# arduino_uno_shield.net
KiCad netlist of a schematic drawn in EAGLE
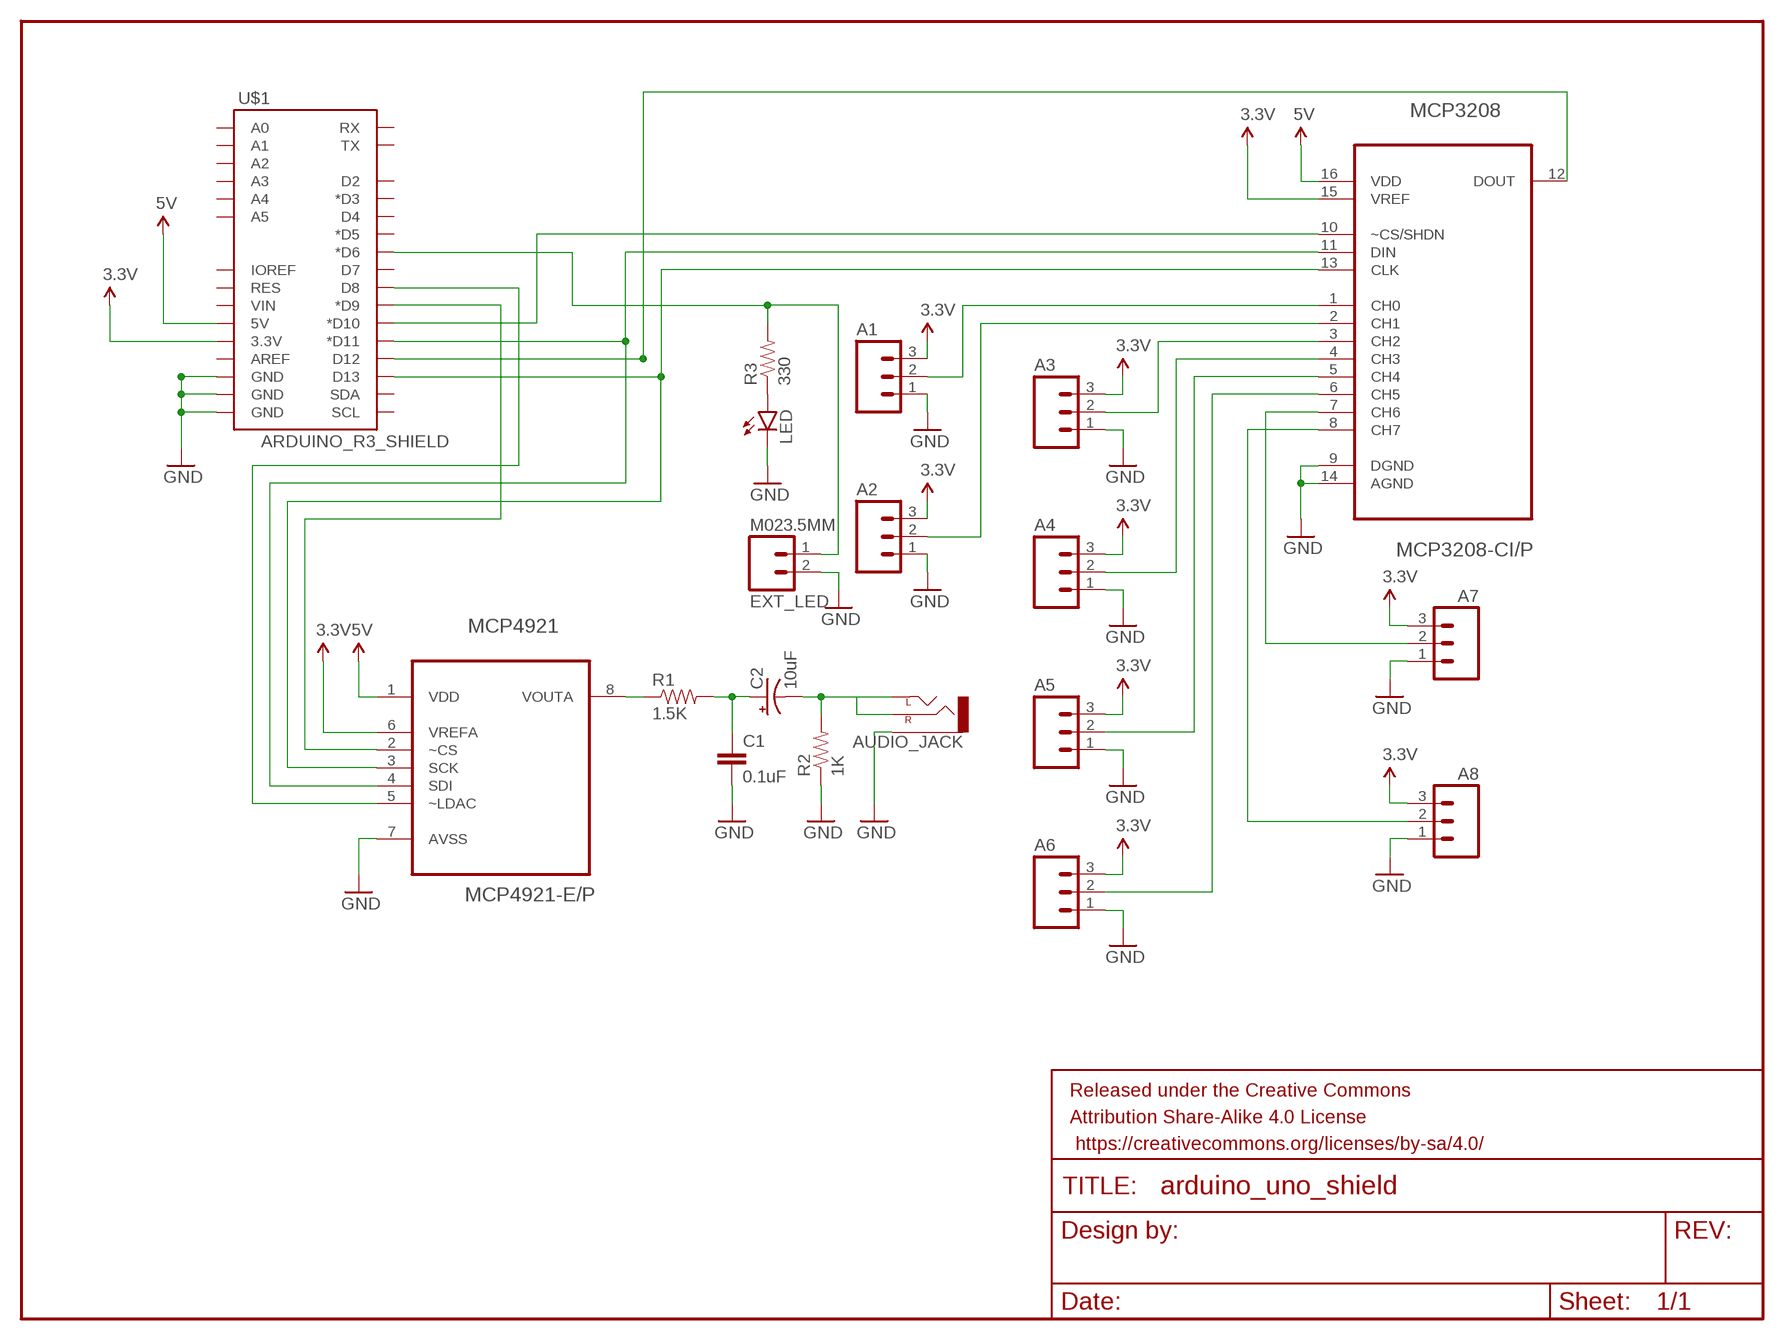
[diagram p0: schematic, sheet 1]

(export (version "E")
  (design (tool "Eeschema 10.0.6"))
  (components
    (comp (ref "A1")
      (value "M03PTH")
      (footprint "eagle-import:1X03")
      (libsource (lib "eagle-import") (part "M03PTH"))
    )
    (comp (ref "A2")
      (value "M03PTH")
      (footprint "eagle-import:1X03")
      (libsource (lib "eagle-import") (part "M03PTH"))
    )
    (comp (ref "A3")
      (value "M03PTH")
      (footprint "eagle-import:1X03")
      (libsource (lib "eagle-import") (part "M03PTH"))
    )
    (comp (ref "A4")
      (value "M03PTH")
      (footprint "eagle-import:1X03")
      (libsource (lib "eagle-import") (part "M03PTH"))
    )
    (comp (ref "A5")
      (value "M03PTH")
      (footprint "eagle-import:1X03")
      (libsource (lib "eagle-import") (part "M03PTH"))
    )
    (comp (ref "A6")
      (value "M03PTH")
      (footprint "eagle-import:1X03")
      (libsource (lib "eagle-import") (part "M03PTH"))
    )
    (comp (ref "A7")
      (value "M03PTH")
      (footprint "eagle-import:1X03")
      (libsource (lib "eagle-import") (part "M03PTH"))
    )
    (comp (ref "A8")
      (value "M03PTH")
      (footprint "eagle-import:1X03")
      (libsource (lib "eagle-import") (part "M03PTH"))
    )
    (comp (ref "AUDIO_JACK")
      (value "AUDIO-JACKPTH")
      (footprint "eagle-import:AUDIO-JACK")
      (libsource (lib "eagle-import") (part "AUDIO-JACKPTH"))
    )
    (comp (ref "C1")
      (value "0.1uF")
      (footprint "eagle-import:CAP-PTH-SMALL")
      (libsource (lib "eagle-import") (part "CAPPTH"))
    )
    (comp (ref "C2")
      (value "10uF")
      (footprint "eagle-import:CPOL-RADIAL-10UF-25V")
      (libsource (lib "eagle-import") (part "CAP_POLPTH2"))
    )
    (comp (ref "EXT_LED")
      (value "M023.5MM")
      (footprint "eagle-import:SCREWTERMINAL-3.5MM-2")
      (libsource (lib "eagle-import") (part "M023.5MM"))
    )
    (comp (ref "FRAME3")
      (value "FRAME-LETTER")
      (footprint "eagle-import:CREATIVE_COMMONS")
      (libsource (lib "eagle-import") (part "FRAME-LETTER"))
    )
    (comp (ref "LED")
      (value "LED5MM")
      (footprint "eagle-import:LED5MM")
      (libsource (lib "eagle-import") (part "LED5MM"))
    )
    (comp (ref "MCP3208")
      (value "MCP3208-CI/P")
      (footprint "eagle-import:DIP254P762X432-16")
      (libsource (lib "eagle-import") (part "MCP3208-CI/P"))
    )
    (comp (ref "MCP4921")
      (value "MCP4921-E/P")
      (footprint "eagle-import:DIP254P762X432-8")
      (libsource (lib "eagle-import") (part "MCP4921-E/P"))
    )
    (comp (ref "R1")
      (value "1.5K")
      (footprint "eagle-import:AXIAL-0.4")
      (libsource (lib "eagle-import") (part "RESISTORPTH-1/4W"))
    )
    (comp (ref "R2")
      (value "1K")
      (footprint "eagle-import:AXIAL-0.4")
      (libsource (lib "eagle-import") (part "RESISTORPTH-1/4W"))
    )
    (comp (ref "R3")
      (value "330")
      (footprint "eagle-import:AXIAL-0.4")
      (libsource (lib "eagle-import") (part "RESISTORPTH-1/4W"))
    )
    (comp (ref "U$1")
      (value "ARDUINO_R3_SHIELD")
      (footprint "eagle-import:UNO_R3_SHIELD")
      (libsource (lib "eagle-import") (part "ARDUINO_R3_SHIELD"))
    )
  )
  (nets
    (net (code "1") (name "3.3V") (class "Default")
      (node (ref "A1") (pin "3") (pinfunction "3_3") (pintype "passive"))
      (node (ref "A2") (pin "3") (pinfunction "3_3") (pintype "passive"))
      (node (ref "A3") (pin "3") (pinfunction "3_3") (pintype "passive"))
      (node (ref "A4") (pin "3") (pinfunction "3_3") (pintype "passive"))
      (node (ref "A5") (pin "3") (pinfunction "3_3") (pintype "passive"))
      (node (ref "A6") (pin "3") (pinfunction "3_3") (pintype "passive"))
      (node (ref "A7") (pin "3") (pinfunction "3_3") (pintype "passive"))
      (node (ref "A8") (pin "3") (pinfunction "3_3") (pintype "passive"))
      (node (ref "MCP3208") (pin "15") (pinfunction "VREF_15") (pintype "power_in"))
      (node (ref "MCP4921") (pin "6") (pinfunction "VREFA_6") (pintype "input"))
      (node (ref "U$1") (pin "3.3V") (pinfunction "3.3V_3.3V") (pintype "bidirectional"))
    )
    (net (code "2") (name "5V") (class "Default")
      (node (ref "MCP3208") (pin "16") (pinfunction "VDD_16") (pintype "power_in"))
      (node (ref "MCP4921") (pin "1") (pinfunction "VDD_1") (pintype "power_in"))
      (node (ref "U$1") (pin "5V") (pinfunction "5V_5V") (pintype "bidirectional"))
    )
    (net (code "3") (name "GND") (class "Default")
      (node (ref "A1") (pin "1") (pinfunction "1_1") (pintype "passive"))
      (node (ref "A2") (pin "1") (pinfunction "1_1") (pintype "passive"))
      (node (ref "A3") (pin "1") (pinfunction "1_1") (pintype "passive"))
      (node (ref "A4") (pin "1") (pinfunction "1_1") (pintype "passive"))
      (node (ref "A5") (pin "1") (pinfunction "1_1") (pintype "passive"))
      (node (ref "A6") (pin "1") (pinfunction "1_1") (pintype "passive"))
      (node (ref "A7") (pin "1") (pinfunction "1_1") (pintype "passive"))
      (node (ref "A8") (pin "1") (pinfunction "1_1") (pintype "passive"))
      (node (ref "AUDIO_JACK") (pin "SLEEVE") (pinfunction "SLEEVE_SLEEVE") (pintype "bidirectional"))
      (node (ref "C1") (pin "2") (pinfunction "2_2") (pintype "passive"))
      (node (ref "EXT_LED") (pin "2") (pinfunction "2_2") (pintype "passive"))
      (node (ref "LED") (pin "K") (pinfunction "C_K") (pintype "passive"))
      (node (ref "MCP3208") (pin "14") (pinfunction "AGND_14") (pintype "passive"))
      (node (ref "MCP3208") (pin "9") (pinfunction "DGND_9") (pintype "passive"))
      (node (ref "MCP4921") (pin "7") (pinfunction "AVSS_7") (pintype "passive"))
      (node (ref "R2") (pin "P$1") (pinfunction "1_P$1") (pintype "passive"))
      (node (ref "U$1") (pin "GND@0") (pinfunction "GND_GND@0") (pintype "bidirectional"))
      (node (ref "U$1") (pin "GND@1") (pinfunction "GND_GND@1") (pintype "bidirectional"))
      (node (ref "U$1") (pin "GND@2") (pinfunction "GND_GND@2") (pintype "bidirectional"))
    )
    (net (code "4") (name "Net-(AUDIO_JACK-LEFT)") (class "Default")
      (node (ref "AUDIO_JACK") (pin "RING") (pinfunction "RIGHT_RING") (pintype "bidirectional"))
      (node (ref "AUDIO_JACK") (pin "TIP") (pinfunction "LEFT_TIP") (pintype "bidirectional"))
      (node (ref "C2") (pin "2") (pinfunction "-_2") (pintype "passive"))
      (node (ref "R2") (pin "P$2") (pinfunction "2_P$2") (pintype "passive"))
    )
    (net (code "5") (name "Net-(C2-+)") (class "Default")
      (node (ref "C1") (pin "1") (pinfunction "1_1") (pintype "passive"))
      (node (ref "C2") (pin "1") (pinfunction "+_1") (pintype "passive"))
      (node (ref "R1") (pin "P$2") (pinfunction "2_P$2") (pintype "passive"))
    )
    (net (code "6") (name "Net-(MCP3208-CH0)") (class "Default")
      (node (ref "A1") (pin "2") (pinfunction "2_2") (pintype "passive"))
      (node (ref "MCP3208") (pin "1") (pinfunction "CH0_1") (pintype "input"))
    )
    (net (code "7") (name "Net-(MCP3208-CH1)") (class "Default")
      (node (ref "A2") (pin "2") (pinfunction "2_2") (pintype "passive"))
      (node (ref "MCP3208") (pin "2") (pinfunction "CH1_2") (pintype "input"))
    )
    (net (code "8") (name "Net-(MCP3208-CH2)") (class "Default")
      (node (ref "A3") (pin "2") (pinfunction "2_2") (pintype "passive"))
      (node (ref "MCP3208") (pin "3") (pinfunction "CH2_3") (pintype "input"))
    )
    (net (code "9") (name "Net-(MCP3208-CH3)") (class "Default")
      (node (ref "A4") (pin "2") (pinfunction "2_2") (pintype "passive"))
      (node (ref "MCP3208") (pin "4") (pinfunction "CH3_4") (pintype "input"))
    )
    (net (code "10") (name "Net-(MCP3208-CH4)") (class "Default")
      (node (ref "A5") (pin "2") (pinfunction "2_2") (pintype "passive"))
      (node (ref "MCP3208") (pin "5") (pinfunction "CH4_5") (pintype "input"))
    )
    (net (code "11") (name "Net-(MCP3208-CH5)") (class "Default")
      (node (ref "A6") (pin "2") (pinfunction "2_2") (pintype "passive"))
      (node (ref "MCP3208") (pin "6") (pinfunction "CH5_6") (pintype "input"))
    )
    (net (code "12") (name "Net-(MCP3208-CH6)") (class "Default")
      (node (ref "A7") (pin "2") (pinfunction "2_2") (pintype "passive"))
      (node (ref "MCP3208") (pin "7") (pinfunction "CH6_7") (pintype "input"))
    )
    (net (code "13") (name "Net-(MCP3208-CH7)") (class "Default")
      (node (ref "A8") (pin "2") (pinfunction "2_2") (pintype "passive"))
      (node (ref "MCP3208") (pin "8") (pinfunction "CH7_8") (pintype "input"))
    )
    (net (code "14") (name "Net-(MCP3208-CLK)") (class "Default")
      (node (ref "MCP3208") (pin "13") (pinfunction "CLK_13") (pintype "input"))
      (node (ref "MCP4921") (pin "3") (pinfunction "SCK_3") (pintype "input"))
      (node (ref "U$1") (pin "D13") (pinfunction "D13_D13") (pintype "bidirectional"))
    )
    (net (code "15") (name "Net-(MCP3208-DIN)") (class "Default")
      (node (ref "MCP3208") (pin "11") (pinfunction "DIN_11") (pintype "input"))
      (node (ref "MCP4921") (pin "4") (pinfunction "SDI_4") (pintype "input"))
      (node (ref "U$1") (pin "D11") (pinfunction "*D11_D11") (pintype "bidirectional"))
    )
    (net (code "16") (name "Net-(MCP3208-DOUT)") (class "Default")
      (node (ref "MCP3208") (pin "12") (pinfunction "DOUT_12") (pintype "output"))
      (node (ref "U$1") (pin "D12") (pinfunction "D12_D12") (pintype "bidirectional"))
    )
    (net (code "17") (name "Net-(MCP3208-~{CS{slash}SHDN})") (class "Default")
      (node (ref "MCP3208") (pin "10") (pinfunction "~{CS/SHDN}_10") (pintype "input"))
      (node (ref "U$1") (pin "D10") (pinfunction "*D10_D10") (pintype "bidirectional"))
    )
    (net (code "18") (name "Net-(MCP4921-VOUTA)") (class "Default")
      (node (ref "MCP4921") (pin "8") (pinfunction "VOUTA_8") (pintype "output"))
      (node (ref "R1") (pin "P$1") (pinfunction "1_P$1") (pintype "passive"))
    )
    (net (code "19") (name "Net-(MCP4921-~{CS})") (class "Default")
      (node (ref "MCP4921") (pin "2") (pinfunction "~{CS}_2") (pintype "input"))
      (node (ref "U$1") (pin "D9") (pinfunction "*D9_D9") (pintype "bidirectional"))
    )
    (net (code "20") (name "Net-(MCP4921-~{LDAC})") (class "Default")
      (node (ref "MCP4921") (pin "5") (pinfunction "~{LDAC}_5") (pintype "input"))
      (node (ref "U$1") (pin "D8") (pinfunction "D8_D8") (pintype "bidirectional"))
    )
    (net (code "21") (name "Net-(R3-1)") (class "Default")
      (node (ref "LED") (pin "A") (pinfunction "A_A") (pintype "passive"))
      (node (ref "R3") (pin "P$1") (pinfunction "1_P$1") (pintype "passive"))
    )
    (net (code "22") (name "Net-(R3-2)") (class "Default")
      (node (ref "EXT_LED") (pin "1") (pinfunction "1_1") (pintype "passive"))
      (node (ref "R3") (pin "P$2") (pinfunction "2_P$2") (pintype "passive"))
      (node (ref "U$1") (pin "D6") (pinfunction "*D6_D6") (pintype "bidirectional"))
    )
    (net (code "23") (name "unconnected-(U$1-*D3-PadD3)") (class "Default")
      (node (ref "U$1") (pin "D3") (pinfunction "*D3_D3") (pintype "bidirectional"))
    )
    (net (code "24") (name "unconnected-(U$1-*D5-PadD5)") (class "Default")
      (node (ref "U$1") (pin "D5") (pinfunction "*D5_D5") (pintype "bidirectional"))
    )
    (net (code "25") (name "unconnected-(U$1-PadA0)") (class "Default")
      (node (ref "U$1") (pin "A0") (pinfunction "A0_A0") (pintype "bidirectional"))
    )
    (net (code "26") (name "unconnected-(U$1-PadA1)") (class "Default")
      (node (ref "U$1") (pin "A1") (pinfunction "A1_A1") (pintype "bidirectional"))
    )
    (net (code "27") (name "unconnected-(U$1-PadA2)") (class "Default")
      (node (ref "U$1") (pin "A2") (pinfunction "A2_A2") (pintype "bidirectional"))
    )
    (net (code "28") (name "unconnected-(U$1-PadA3)") (class "Default")
      (node (ref "U$1") (pin "A3") (pinfunction "A3_A3") (pintype "bidirectional"))
    )
    (net (code "29") (name "unconnected-(U$1-PadA4)") (class "Default")
      (node (ref "U$1") (pin "A4") (pinfunction "A4_A4") (pintype "bidirectional"))
    )
    (net (code "30") (name "unconnected-(U$1-PadA5)") (class "Default")
      (node (ref "U$1") (pin "A5") (pinfunction "A5_A5") (pintype "bidirectional"))
    )
    (net (code "31") (name "unconnected-(U$1-PadAREF)") (class "Default")
      (node (ref "U$1") (pin "AREF") (pinfunction "AREF_AREF") (pintype "bidirectional"))
    )
    (net (code "32") (name "unconnected-(U$1-PadD2)") (class "Default")
      (node (ref "U$1") (pin "D2") (pinfunction "D2_D2") (pintype "bidirectional"))
    )
    (net (code "33") (name "unconnected-(U$1-PadD4)") (class "Default")
      (node (ref "U$1") (pin "D4") (pinfunction "D4_D4") (pintype "bidirectional"))
    )
    (net (code "34") (name "unconnected-(U$1-PadD7)") (class "Default")
      (node (ref "U$1") (pin "D7") (pinfunction "D7_D7") (pintype "bidirectional"))
    )
    (net (code "35") (name "unconnected-(U$1-PadIOREF)") (class "Default")
      (node (ref "U$1") (pin "IOREF") (pinfunction "IOREF_IOREF") (pintype "bidirectional"))
    )
    (net (code "36") (name "unconnected-(U$1-PadRES)") (class "Default")
      (node (ref "U$1") (pin "RES") (pinfunction "RES_RES") (pintype "bidirectional"))
    )
    (net (code "37") (name "unconnected-(U$1-PadRX)") (class "Default")
      (node (ref "U$1") (pin "RX") (pinfunction "RX_RX") (pintype "bidirectional"))
    )
    (net (code "38") (name "unconnected-(U$1-PadSCL)") (class "Default")
      (node (ref "U$1") (pin "SCL") (pinfunction "SCL_SCL") (pintype "bidirectional"))
    )
    (net (code "39") (name "unconnected-(U$1-PadSDA)") (class "Default")
      (node (ref "U$1") (pin "SDA") (pinfunction "SDA_SDA") (pintype "bidirectional"))
    )
    (net (code "40") (name "unconnected-(U$1-PadTX)") (class "Default")
      (node (ref "U$1") (pin "TX") (pinfunction "TX_TX") (pintype "bidirectional"))
    )
    (net (code "41") (name "unconnected-(U$1-PadVIN)") (class "Default")
      (node (ref "U$1") (pin "VIN") (pinfunction "VIN_VIN") (pintype "bidirectional"))
    )
  )
)
